# drvoutput4.net
KiCad netlist of a schematic drawn in Altium Designer
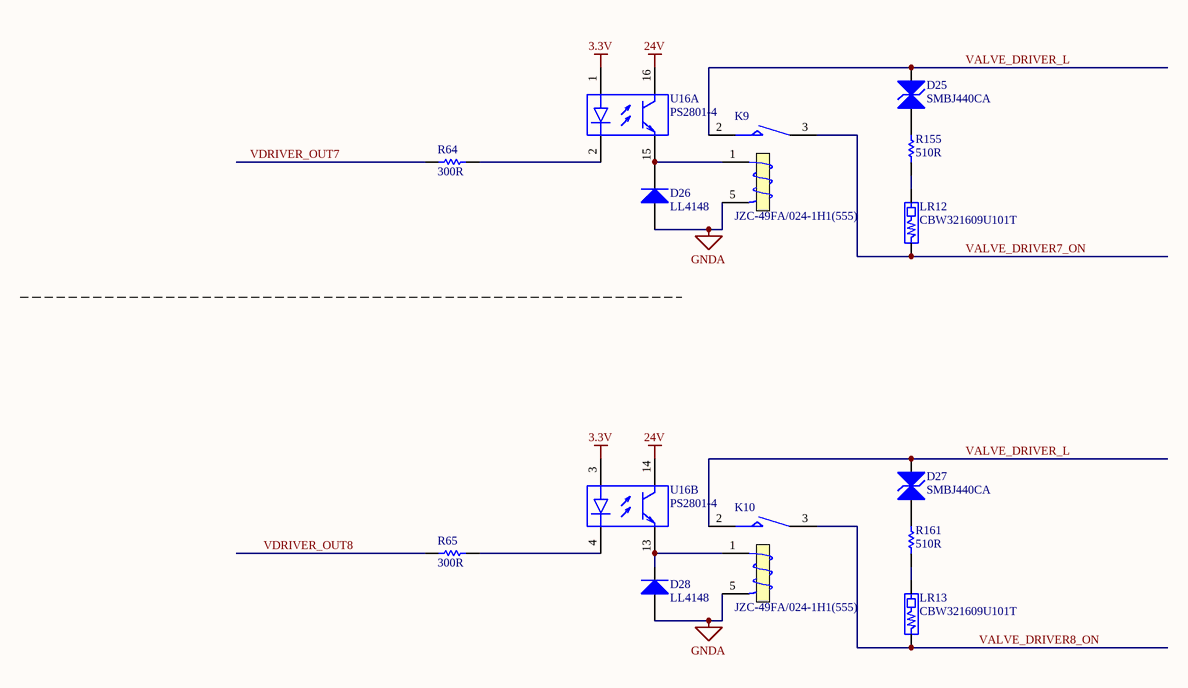
[diagram p0: drvoutput4.SchDoc]

(export (version "E")
  (design (tool "Eeschema 10.0.6"))
  (components
    (comp (ref "D25")
      (value "SMBJ440CA")
      (footprint "SMB")
      (description "Bi-dir TVS Diode")
      (fields (field (name "PUBLISHER") "Altium Limited"))
      (libsource (lib "UserLib") (part "Bi-dir TVS Diode"))
    )
    (comp (ref "D26")
      (value "LL4148")
      (footprint "CD2012-0805")
      (description "1 Amp General Purpose Rectifier")
      (fields (field (name "PUBLISHER") "Altium Limited"))
      (libsource (lib "Miscellaneous Devices") (part "Diode 1N4007"))
    )
    (comp (ref "D27")
      (value "SMBJ440CA")
      (footprint "SMB")
      (description "Bi-dir TVS Diode")
      (fields (field (name "PUBLISHER") "Altium Limited"))
      (libsource (lib "UserLib") (part "Bi-dir TVS Diode"))
    )
    (comp (ref "D28")
      (value "LL4148")
      (footprint "CD2012-0805")
      (description "1 Amp General Purpose Rectifier")
      (fields (field (name "PUBLISHER") "Altium Limited"))
      (libsource (lib "Miscellaneous Devices") (part "Diode 1N4007"))
    )
    (comp (ref "K9")
      (value "JZC-49FA/024-1H1(555)")
      (footprint "JZC-49FA")
      (description "Intermediate  Power  Relay")
      (fields (field (name "PUBLISHER") "Altium Limited"))
      (libsource (lib "UserSchDev") (part "JZC-49FA"))
    )
    (comp (ref "K10")
      (value "JZC-49FA/024-1H1(555)")
      (footprint "JZC-49FA")
      (description "Intermediate  Power  Relay")
      (fields (field (name "PUBLISHER") "Altium Limited"))
      (libsource (lib "UserSchDev") (part "JZC-49FA"))
    )
    (comp (ref "LR12")
      (value "CBW321609U101T")
      (footprint "INDC3216M")
      (description "EMI FILTERS,DC Resistance max.0.05~1.5 ohms,10 ~ 1000 ohms at 100MHz  Frequency")
      (libsource (lib "UserLib") (part "BLM10/11/21/31/41"))
    )
    (comp (ref "LR13")
      (value "CBW321609U101T")
      (footprint "INDC3216M")
      (description "EMI FILTERS,DC Resistance max.0.05~1.5 ohms,10 ~ 1000 ohms at 100MHz  Frequency")
      (libsource (lib "UserLib") (part "BLM10/11/21/31/41"))
    )
    (comp (ref "R64")
      (value "300R")
      (footprint "RESC2012M")
      (description "Resistor")
      (fields (field (name "PUBLISHER") "Altium Limited"))
      (libsource (lib "Miscellaneous Devices") (part "Res1"))
    )
    (comp (ref "R65")
      (value "300R")
      (footprint "RESC2012M")
      (description "Resistor")
      (fields (field (name "PUBLISHER") "Altium Limited"))
      (libsource (lib "Miscellaneous Devices") (part "Res1"))
    )
    (comp (ref "R155")
      (value "510R")
      (footprint "RESC3216M")
      (description "Metal film Resistor")
      (fields (field (name "PUBLISHER") "Altium Limited"))
      (libsource (lib "Miscellaneous Devices") (part "Res1"))
    )
    (comp (ref "R161")
      (value "510R")
      (footprint "RESC3216M")
      (description "Metal film Resistor")
      (fields (field (name "PUBLISHER") "Altium Limited"))
      (libsource (lib "Miscellaneous Devices") (part "Res1"))
    )
    (comp (ref "U16")
      (value "PS2801-4")
      (footprint "SOIC16_N")
      (fields (field (name "PUBLISHER") "Altium Limited"))
      (libsource (lib "UserSchDev") (part "PS2801-4"))
    )
  )
  (nets
    (net (code "1") (name "/VALVE_DRIVER7_ON") (class "Default")
      (node (ref "K9") (pin "3") (pinfunction "NO_3") (pintype "passive"))
      (node (ref "LR12") (pin "1") (pinfunction "1_1") (pintype "passive"))
    )
    (net (code "2") (name "/VALVE_DRIVER8_ON") (class "Default")
      (node (ref "K10") (pin "3") (pinfunction "NO_3") (pintype "passive"))
      (node (ref "LR13") (pin "1") (pinfunction "1_1") (pintype "passive"))
    )
    (net (code "3") (name "/VALVE_DRIVER_L") (class "Default")
      (node (ref "D25") (pin "2") (pinfunction "K_2") (pintype "passive"))
      (node (ref "D27") (pin "2") (pinfunction "K_2") (pintype "passive"))
      (node (ref "K10") (pin "2") (pinfunction "COM_2") (pintype "passive"))
      (node (ref "K9") (pin "2") (pinfunction "COM_2") (pintype "passive"))
    )
    (net (code "4") (name "/VDRIVER_OUT7") (class "Default")
      (node (ref "R64") (pin "1") (pinfunction "1_1") (pintype "passive"))
    )
    (net (code "5") (name "/VDRIVER_OUT8") (class "Default")
      (node (ref "R65") (pin "1") (pinfunction "1_1") (pintype "passive"))
    )
    (net (code "6") (name "3.3V") (class "Default")
      (node (ref "U16") (pin "1") (pinfunction "+_1") (pintype "passive"))
      (node (ref "U16") (pin "3") (pinfunction "+_3") (pintype "passive"))
    )
    (net (code "7") (name "24V") (class "Default")
      (node (ref "U16") (pin "14") (pinfunction "C_14") (pintype "passive"))
      (node (ref "U16") (pin "16") (pinfunction "C_16") (pintype "passive"))
    )
    (net (code "8") (name "GNDA") (class "Default")
      (node (ref "D26") (pin "1") (pinfunction "A_1") (pintype "passive"))
      (node (ref "D28") (pin "1") (pinfunction "A_1") (pintype "passive"))
      (node (ref "K10") (pin "5") (pinfunction "T2_5") (pintype "passive"))
      (node (ref "K9") (pin "5") (pinfunction "T2_5") (pintype "passive"))
    )
    (net (code "9") (name "Net-(D25-A)") (class "Default")
      (node (ref "D25") (pin "1") (pinfunction "A_1") (pintype "passive"))
      (node (ref "R155") (pin "2") (pinfunction "2_2") (pintype "passive"))
    )
    (net (code "10") (name "Net-(D26-K)") (class "Default")
      (node (ref "D26") (pin "2") (pinfunction "K_2") (pintype "passive"))
      (node (ref "K9") (pin "1") (pinfunction "1_1") (pintype "passive"))
      (node (ref "U16") (pin "15") (pinfunction "E_15") (pintype "passive"))
    )
    (net (code "11") (name "Net-(D27-A)") (class "Default")
      (node (ref "D27") (pin "1") (pinfunction "A_1") (pintype "passive"))
      (node (ref "R161") (pin "2") (pinfunction "2_2") (pintype "passive"))
    )
    (net (code "12") (name "Net-(D28-K)") (class "Default")
      (node (ref "D28") (pin "2") (pinfunction "K_2") (pintype "passive"))
      (node (ref "K10") (pin "1") (pinfunction "1_1") (pintype "passive"))
      (node (ref "U16") (pin "13") (pinfunction "E_13") (pintype "passive"))
    )
    (net (code "13") (name "Net-(LR12-Pad2)") (class "Default")
      (node (ref "LR12") (pin "2") (pinfunction "2_2") (pintype "passive"))
      (node (ref "R155") (pin "1") (pinfunction "1_1") (pintype "passive"))
    )
    (net (code "14") (name "Net-(LR13-Pad2)") (class "Default")
      (node (ref "LR13") (pin "2") (pinfunction "2_2") (pintype "passive"))
      (node (ref "R161") (pin "1") (pinfunction "1_1") (pintype "passive"))
    )
    (net (code "15") (name "Net-(U16A--)") (class "Default")
      (node (ref "R64") (pin "2") (pinfunction "2_2") (pintype "passive"))
      (node (ref "U16") (pin "2") (pinfunction "-_2") (pintype "passive"))
    )
    (net (code "16") (name "Net-(U16B--)") (class "Default")
      (node (ref "R65") (pin "2") (pinfunction "2_2") (pintype "passive"))
      (node (ref "U16") (pin "4") (pinfunction "-_4") (pintype "passive"))
    )
  )
)
